# switching_reg.net
KiCad netlist of a schematic drawn in EAGLE
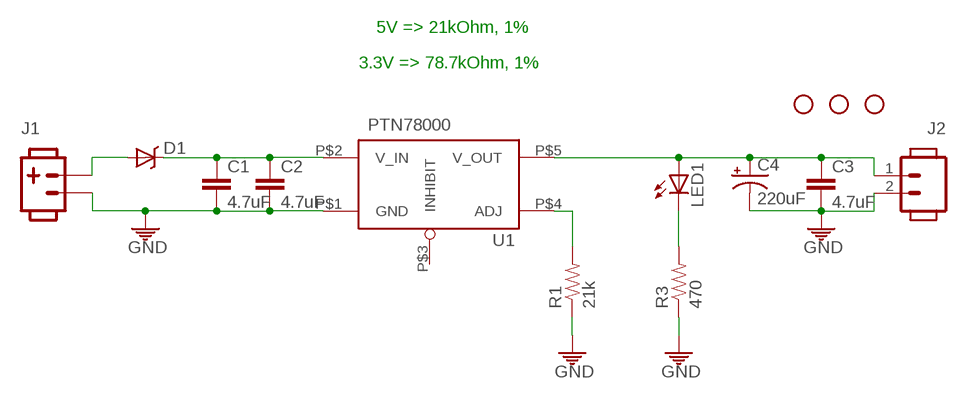
[diagram p0: schematic, sheet 1]

(export (version "E")
  (design (tool "Eeschema 10.0.6"))
  (components
    (comp (ref "C1")
      (value "4.7uF")
      (footprint "eagle-import:1206")
      (libsource (lib "eagle-import") (part "CAP1206"))
    )
    (comp (ref "C2")
      (value "4.7uF")
      (footprint "eagle-import:1206")
      (libsource (lib "eagle-import") (part "CAP1206"))
    )
    (comp (ref "C3")
      (value "4.7uF")
      (footprint "eagle-import:1206")
      (libsource (lib "eagle-import") (part "CAP1206"))
    )
    (comp (ref "C4")
      (value "220uF")
      (footprint "eagle-import:CPOL_6.6")
      (libsource (lib "eagle-import") (part "CAP_POL"))
    )
    (comp (ref "D1")
      (value "DIODE-SCHOTTKY240A")
      (footprint "eagle-import:SMA-DIODE-B240A")
      (libsource (lib "eagle-import") (part "DIODE-SCHOTTKY240A"))
    )
    (comp (ref "J1")
      (value "POW_CONNECTMALE")
      (footprint "eagle-import:SOCKET-MALE-3.96MM-2")
      (libsource (lib "eagle-import") (part "POW_CONNECTMALE"))
    )
    (comp (ref "J2")
      (value "SCREWTERM02")
      (footprint "eagle-import:SCREW_TERMINAL-5.08MM-2")
      (libsource (lib "eagle-import") (part "SCREWTERM02"))
    )
    (comp (ref "JP1")
      (value "STAND-OFFTIGHT")
      (footprint "eagle-import:STAND-OFF-TIGHT")
      (libsource (lib "eagle-import") (part "STAND-OFFTIGHT"))
    )
    (comp (ref "JP2")
      (value "STAND-OFFTIGHT")
      (footprint "eagle-import:STAND-OFF-TIGHT")
      (libsource (lib "eagle-import") (part "STAND-OFFTIGHT"))
    )
    (comp (ref "JP3")
      (value "STAND-OFFTIGHT")
      (footprint "eagle-import:STAND-OFF-TIGHT")
      (libsource (lib "eagle-import") (part "STAND-OFFTIGHT"))
    )
    (comp (ref "LED1")
      (value "LED1206")
      (footprint "eagle-import:LED-1206")
      (libsource (lib "eagle-import") (part "LED1206"))
    )
    (comp (ref "R1")
      (value "21k")
      (footprint "eagle-import:0805")
      (libsource (lib "eagle-import") (part "RESISTOR0805-RES"))
    )
    (comp (ref "R3")
      (value "470")
      (footprint "eagle-import:0805")
      (libsource (lib "eagle-import") (part "RESISTOR0805-RES"))
    )
    (comp (ref "U1")
      (value "PTN78000")
      (footprint "eagle-import:PTN78000_SM")
      (libsource (lib "eagle-import") (part "PTN78000SURFACE-MOUNT"))
    )
  )
  (nets
    (net (code "1") (name "GND") (class "Default")
      (node (ref "C1") (pin "2") (pinfunction "2_2") (pintype "passive"))
      (node (ref "C2") (pin "2") (pinfunction "2_2") (pintype "passive"))
      (node (ref "C3") (pin "2") (pinfunction "2_2") (pintype "passive"))
      (node (ref "C4") (pin "-") (pinfunction "-_-") (pintype "passive"))
      (node (ref "J1") (pin "P$2") (pinfunction "2_P$2") (pintype "passive"))
      (node (ref "J2") (pin "2") (pinfunction "2_2") (pintype "passive"))
      (node (ref "R1") (pin "1") (pinfunction "1_1") (pintype "passive"))
      (node (ref "R3") (pin "1") (pinfunction "1_1") (pintype "passive"))
      (node (ref "U1") (pin "P$1") (pinfunction "GND_P$1") (pintype "power_in"))
    )
    (net (code "2") (name "Net-(J1-1)") (class "Default")
      (node (ref "D1") (pin "A") (pinfunction "A_A") (pintype "passive"))
      (node (ref "J1") (pin "P$1") (pinfunction "1_P$1") (pintype "passive"))
    )
    (net (code "3") (name "Net-(LED1-PadC)") (class "Default")
      (node (ref "LED1") (pin "C") (pinfunction "C_C") (pintype "passive"))
      (node (ref "R3") (pin "2") (pinfunction "2_2") (pintype "passive"))
    )
    (net (code "4") (name "Net-(U1-ADJ)") (class "Default")
      (node (ref "R1") (pin "2") (pinfunction "2_2") (pintype "passive"))
      (node (ref "U1") (pin "P$4") (pinfunction "ADJ_P$4") (pintype "input"))
    )
    (net (code "5") (name "Net-(U1-V_IN)") (class "Default")
      (node (ref "C1") (pin "1") (pinfunction "1_1") (pintype "passive"))
      (node (ref "C2") (pin "1") (pinfunction "1_1") (pintype "passive"))
      (node (ref "D1") (pin "C") (pinfunction "C_C") (pintype "passive"))
      (node (ref "U1") (pin "P$2") (pinfunction "V_IN_P$2") (pintype "power_in"))
    )
    (net (code "6") (name "Net-(U1-V_OUT)") (class "Default")
      (node (ref "C3") (pin "1") (pinfunction "1_1") (pintype "passive"))
      (node (ref "C4") (pin "+") (pinfunction "+_+") (pintype "passive"))
      (node (ref "J2") (pin "1") (pinfunction "1_1") (pintype "passive"))
      (node (ref "LED1") (pin "A") (pinfunction "A_A") (pintype "passive"))
      (node (ref "U1") (pin "P$5") (pinfunction "V_OUT_P$5") (pintype "output"))
    )
    (net (code "7") (name "unconnected-(U1-INHIBIT-PadP$3)") (class "Default")
      (node (ref "U1") (pin "P$3") (pinfunction "INHIBIT_P$3") (pintype "input"))
    )
  )
)
